# EuroProtoFront.net
KiCad netlist of a schematic drawn in EAGLE
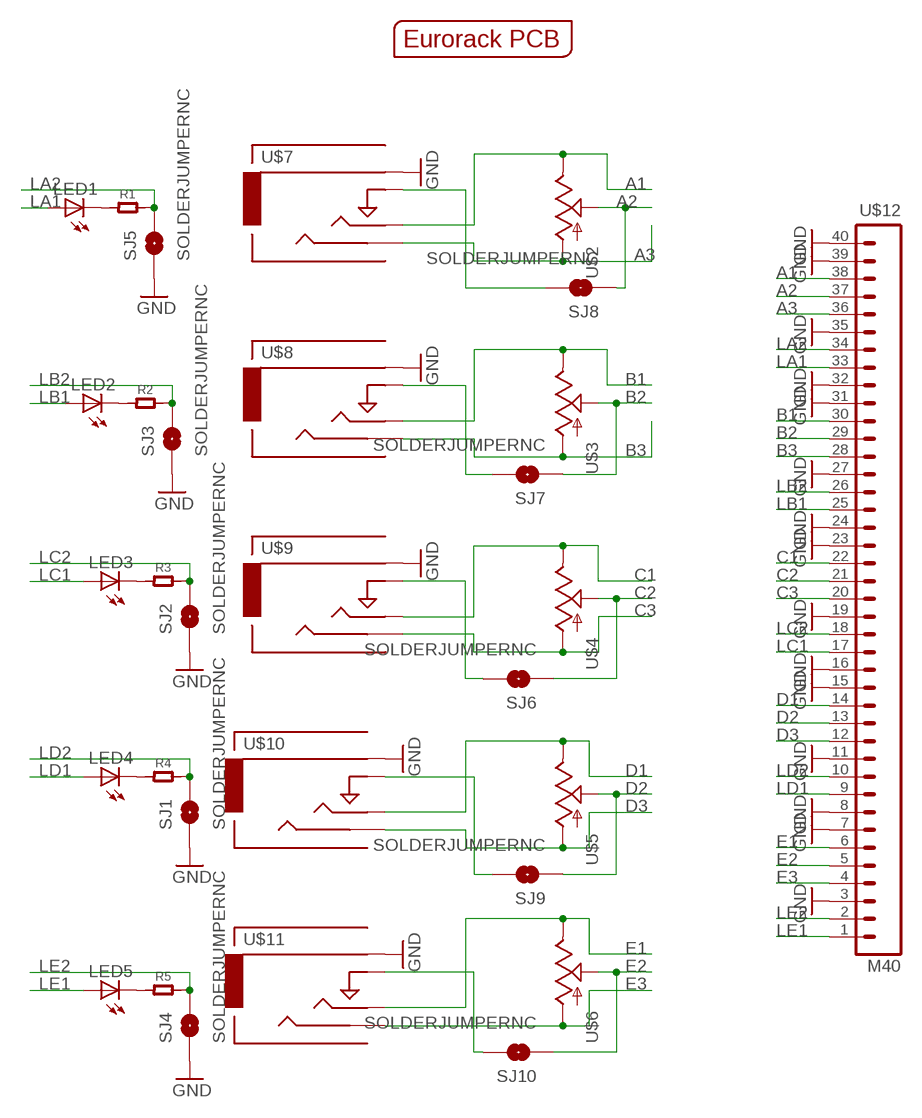
[diagram p0: schematic, sheet 1]

(export (version "E")
  (design (tool "Eeschema 10.0.6"))
  (components
    (comp (ref "LED1")
      (value "LED3MM")
      (footprint "eagle-import:LED3MM")
      (libsource (lib "eagle-import") (part "LED3MM"))
    )
    (comp (ref "LED2")
      (value "LED3MM")
      (footprint "eagle-import:LED3MM")
      (libsource (lib "eagle-import") (part "LED3MM"))
    )
    (comp (ref "LED3")
      (value "LED3MM")
      (footprint "eagle-import:LED3MM")
      (libsource (lib "eagle-import") (part "LED3MM"))
    )
    (comp (ref "LED4")
      (value "LED3MM")
      (footprint "eagle-import:LED3MM")
      (libsource (lib "eagle-import") (part "LED3MM"))
    )
    (comp (ref "LED5")
      (value "LED3MM")
      (footprint "eagle-import:LED3MM")
      (libsource (lib "eagle-import") (part "LED3MM"))
    )
    (comp (ref "R1")
      (value "R-0603")
      (footprint "eagle-import:R0603")
      (libsource (lib "eagle-import") (part "R-0603"))
    )
    (comp (ref "R2")
      (value "R-0603")
      (footprint "eagle-import:R0603")
      (libsource (lib "eagle-import") (part "R-0603"))
    )
    (comp (ref "R3")
      (value "R-0603")
      (footprint "eagle-import:R0603")
      (libsource (lib "eagle-import") (part "R-0603"))
    )
    (comp (ref "R4")
      (value "R-0603")
      (footprint "eagle-import:R0603")
      (libsource (lib "eagle-import") (part "R-0603"))
    )
    (comp (ref "R5")
      (value "R-0603")
      (footprint "eagle-import:R0603")
      (libsource (lib "eagle-import") (part "R-0603"))
    )
    (comp (ref "SJ1")
      (value "SOLDERJUMPERNC")
      (footprint "eagle-import:SJ_2S")
      (libsource (lib "eagle-import") (part "SOLDERJUMPERNC"))
    )
    (comp (ref "SJ2")
      (value "SOLDERJUMPERNC")
      (footprint "eagle-import:SJ_2S")
      (libsource (lib "eagle-import") (part "SOLDERJUMPERNC"))
    )
    (comp (ref "SJ3")
      (value "SOLDERJUMPERNC")
      (footprint "eagle-import:SJ_2S")
      (libsource (lib "eagle-import") (part "SOLDERJUMPERNC"))
    )
    (comp (ref "SJ4")
      (value "SOLDERJUMPERNC")
      (footprint "eagle-import:SJ_2S")
      (libsource (lib "eagle-import") (part "SOLDERJUMPERNC"))
    )
    (comp (ref "SJ5")
      (value "SOLDERJUMPERNC")
      (footprint "eagle-import:SJ_2S")
      (libsource (lib "eagle-import") (part "SOLDERJUMPERNC"))
    )
    (comp (ref "SJ6")
      (value "SOLDERJUMPERNC")
      (footprint "eagle-import:SJ_2S")
      (libsource (lib "eagle-import") (part "SOLDERJUMPERNC"))
    )
    (comp (ref "SJ7")
      (value "SOLDERJUMPERNC")
      (footprint "eagle-import:SJ_2S")
      (libsource (lib "eagle-import") (part "SOLDERJUMPERNC"))
    )
    (comp (ref "SJ8")
      (value "SOLDERJUMPERNC")
      (footprint "eagle-import:SJ_2S")
      (libsource (lib "eagle-import") (part "SOLDERJUMPERNC"))
    )
    (comp (ref "SJ9")
      (value "SOLDERJUMPERNC")
      (footprint "eagle-import:SJ_2S")
      (libsource (lib "eagle-import") (part "SOLDERJUMPERNC"))
    )
    (comp (ref "SJ10")
      (value "SOLDERJUMPERNC")
      (footprint "eagle-import:SJ_2S")
      (libsource (lib "eagle-import") (part "SOLDERJUMPERNC"))
    )
    (comp (ref "U$1")
      (value "EURORACK_PCB4HP")
      (footprint "eagle-import:EURORACK4HPPCB")
      (libsource (lib "eagle-import") (part "EURORACK_PCB4HP"))
    )
    (comp (ref "U$2")
      (value "POTZEPHPOT")
      (footprint "eagle-import:OG-POTS_ALPS_POT_VERTICAL")
      (libsource (lib "eagle-import") (part "POTZEPHPOT"))
    )
    (comp (ref "U$3")
      (value "POTZEPHPOT")
      (footprint "eagle-import:OG-POTS_ALPS_POT_VERTICAL")
      (libsource (lib "eagle-import") (part "POTZEPHPOT"))
    )
    (comp (ref "U$4")
      (value "POTZEPHPOT")
      (footprint "eagle-import:OG-POTS_ALPS_POT_VERTICAL")
      (libsource (lib "eagle-import") (part "POTZEPHPOT"))
    )
    (comp (ref "U$5")
      (value "POTZEPHPOT")
      (footprint "eagle-import:OG-POTS_ALPS_POT_VERTICAL")
      (libsource (lib "eagle-import") (part "POTZEPHPOT"))
    )
    (comp (ref "U$6")
      (value "POTZEPHPOT")
      (footprint "eagle-import:OG-POTS_ALPS_POT_VERTICAL")
      (libsource (lib "eagle-import") (part "POTZEPHPOT"))
    )
    (comp (ref "U$7")
      (value "AUDIO-JACKINPUT")
      (footprint "eagle-import:3.5MM-JACK-SWITCH-13MM-INPUT")
      (libsource (lib "eagle-import") (part "AUDIO-JACKINPUT"))
    )
    (comp (ref "U$8")
      (value "AUDIO-JACKINPUT")
      (footprint "eagle-import:3.5MM-JACK-SWITCH-13MM-INPUT")
      (libsource (lib "eagle-import") (part "AUDIO-JACKINPUT"))
    )
    (comp (ref "U$9")
      (value "AUDIO-JACKINPUT")
      (footprint "eagle-import:3.5MM-JACK-SWITCH-13MM-INPUT")
      (libsource (lib "eagle-import") (part "AUDIO-JACKINPUT"))
    )
    (comp (ref "U$10")
      (value "AUDIO-JACKINPUT")
      (footprint "eagle-import:3.5MM-JACK-SWITCH-13MM-INPUT")
      (libsource (lib "eagle-import") (part "AUDIO-JACKINPUT"))
    )
    (comp (ref "U$11")
      (value "AUDIO-JACKINPUT")
      (footprint "eagle-import:3.5MM-JACK-SWITCH-13MM-INPUT")
      (libsource (lib "eagle-import") (part "AUDIO-JACKINPUT"))
    )
    (comp (ref "U$12")
      (value "M40")
      (footprint "eagle-import:1X40")
      (libsource (lib "eagle-import") (part "M40"))
    )
  )
  (nets
    (net (code "1") (name "/A1") (class "Default")
      (node (ref "U$12") (pin "38") (pinfunction "38_38") (pintype "passive"))
      (node (ref "U$2") (pin "P$1") (pinfunction "E_P$1") (pintype "passive"))
      (node (ref "U$7") (pin "TIP@1") (pinfunction "TIP_TIP@1") (pintype "bidirectional"))
      (node (ref "U$7") (pin "TIP@2") (pinfunction "TIP_TIP@2") (pintype "bidirectional"))
    )
    (net (code "2") (name "/A2") (class "Default")
      (node (ref "SJ8") (pin "1") (pinfunction "1_1") (pintype "passive"))
      (node (ref "U$12") (pin "37") (pinfunction "37_37") (pintype "passive"))
      (node (ref "U$2") (pin "P$2") (pinfunction "S_P$2") (pintype "passive"))
    )
    (net (code "3") (name "/A3") (class "Default")
      (node (ref "U$12") (pin "36") (pinfunction "36_36") (pintype "passive"))
      (node (ref "U$2") (pin "P$3") (pinfunction "A_P$3") (pintype "passive"))
      (node (ref "U$7") (pin "SECOND@1") (pinfunction "SECOND_SECOND@1") (pintype "bidirectional"))
      (node (ref "U$7") (pin "SECOND@2") (pinfunction "SECOND_SECOND@2") (pintype "bidirectional"))
    )
    (net (code "4") (name "/B1") (class "Default")
      (node (ref "U$12") (pin "30") (pinfunction "30_30") (pintype "passive"))
      (node (ref "U$3") (pin "P$1") (pinfunction "E_P$1") (pintype "passive"))
      (node (ref "U$8") (pin "TIP@1") (pinfunction "TIP_TIP@1") (pintype "bidirectional"))
      (node (ref "U$8") (pin "TIP@2") (pinfunction "TIP_TIP@2") (pintype "bidirectional"))
    )
    (net (code "5") (name "/B2") (class "Default")
      (node (ref "SJ7") (pin "1") (pinfunction "1_1") (pintype "passive"))
      (node (ref "U$12") (pin "29") (pinfunction "29_29") (pintype "passive"))
      (node (ref "U$3") (pin "P$2") (pinfunction "S_P$2") (pintype "passive"))
    )
    (net (code "6") (name "/B3") (class "Default")
      (node (ref "U$12") (pin "28") (pinfunction "28_28") (pintype "passive"))
      (node (ref "U$3") (pin "P$3") (pinfunction "A_P$3") (pintype "passive"))
      (node (ref "U$8") (pin "SECOND@1") (pinfunction "SECOND_SECOND@1") (pintype "bidirectional"))
      (node (ref "U$8") (pin "SECOND@2") (pinfunction "SECOND_SECOND@2") (pintype "bidirectional"))
    )
    (net (code "7") (name "/C1") (class "Default")
      (node (ref "U$12") (pin "22") (pinfunction "22_22") (pintype "passive"))
      (node (ref "U$4") (pin "P$1") (pinfunction "E_P$1") (pintype "passive"))
      (node (ref "U$9") (pin "TIP@1") (pinfunction "TIP_TIP@1") (pintype "bidirectional"))
      (node (ref "U$9") (pin "TIP@2") (pinfunction "TIP_TIP@2") (pintype "bidirectional"))
    )
    (net (code "8") (name "/C2") (class "Default")
      (node (ref "SJ6") (pin "1") (pinfunction "1_1") (pintype "passive"))
      (node (ref "U$12") (pin "21") (pinfunction "21_21") (pintype "passive"))
      (node (ref "U$4") (pin "P$2") (pinfunction "S_P$2") (pintype "passive"))
    )
    (net (code "9") (name "/C3") (class "Default")
      (node (ref "U$12") (pin "20") (pinfunction "20_20") (pintype "passive"))
      (node (ref "U$4") (pin "P$3") (pinfunction "A_P$3") (pintype "passive"))
      (node (ref "U$9") (pin "SECOND@1") (pinfunction "SECOND_SECOND@1") (pintype "bidirectional"))
      (node (ref "U$9") (pin "SECOND@2") (pinfunction "SECOND_SECOND@2") (pintype "bidirectional"))
    )
    (net (code "10") (name "/D1") (class "Default")
      (node (ref "U$10") (pin "TIP@1") (pinfunction "TIP_TIP@1") (pintype "bidirectional"))
      (node (ref "U$10") (pin "TIP@2") (pinfunction "TIP_TIP@2") (pintype "bidirectional"))
      (node (ref "U$12") (pin "14") (pinfunction "14_14") (pintype "passive"))
      (node (ref "U$5") (pin "P$1") (pinfunction "E_P$1") (pintype "passive"))
    )
    (net (code "11") (name "/D2") (class "Default")
      (node (ref "SJ9") (pin "1") (pinfunction "1_1") (pintype "passive"))
      (node (ref "U$12") (pin "13") (pinfunction "13_13") (pintype "passive"))
      (node (ref "U$5") (pin "P$2") (pinfunction "S_P$2") (pintype "passive"))
    )
    (net (code "12") (name "/D3") (class "Default")
      (node (ref "U$10") (pin "SECOND@1") (pinfunction "SECOND_SECOND@1") (pintype "bidirectional"))
      (node (ref "U$10") (pin "SECOND@2") (pinfunction "SECOND_SECOND@2") (pintype "bidirectional"))
      (node (ref "U$12") (pin "12") (pinfunction "12_12") (pintype "passive"))
      (node (ref "U$5") (pin "P$3") (pinfunction "A_P$3") (pintype "passive"))
    )
    (net (code "13") (name "/E1") (class "Default")
      (node (ref "U$11") (pin "TIP@1") (pinfunction "TIP_TIP@1") (pintype "bidirectional"))
      (node (ref "U$11") (pin "TIP@2") (pinfunction "TIP_TIP@2") (pintype "bidirectional"))
      (node (ref "U$12") (pin "6") (pinfunction "6_6") (pintype "passive"))
      (node (ref "U$6") (pin "P$1") (pinfunction "E_P$1") (pintype "passive"))
    )
    (net (code "14") (name "/E2") (class "Default")
      (node (ref "SJ10") (pin "1") (pinfunction "1_1") (pintype "passive"))
      (node (ref "U$12") (pin "5") (pinfunction "5_5") (pintype "passive"))
      (node (ref "U$6") (pin "P$2") (pinfunction "S_P$2") (pintype "passive"))
    )
    (net (code "15") (name "/E3") (class "Default")
      (node (ref "U$11") (pin "SECOND@1") (pinfunction "SECOND_SECOND@1") (pintype "bidirectional"))
      (node (ref "U$11") (pin "SECOND@2") (pinfunction "SECOND_SECOND@2") (pintype "bidirectional"))
      (node (ref "U$12") (pin "4") (pinfunction "4_4") (pintype "passive"))
      (node (ref "U$6") (pin "P$3") (pinfunction "A_P$3") (pintype "passive"))
    )
    (net (code "16") (name "/LA1") (class "Default")
      (node (ref "LED1") (pin "A") (pinfunction "A_A") (pintype "passive"))
      (node (ref "U$12") (pin "33") (pinfunction "33_33") (pintype "passive"))
    )
    (net (code "17") (name "/LA2") (class "Default")
      (node (ref "R1") (pin "2") (pinfunction "2_2") (pintype "bidirectional"))
      (node (ref "SJ5") (pin "2") (pinfunction "2_2") (pintype "passive"))
      (node (ref "U$12") (pin "34") (pinfunction "34_34") (pintype "passive"))
    )
    (net (code "18") (name "/LB1") (class "Default")
      (node (ref "LED2") (pin "A") (pinfunction "A_A") (pintype "passive"))
      (node (ref "U$12") (pin "25") (pinfunction "25_25") (pintype "passive"))
    )
    (net (code "19") (name "/LB2") (class "Default")
      (node (ref "R2") (pin "2") (pinfunction "2_2") (pintype "bidirectional"))
      (node (ref "SJ3") (pin "2") (pinfunction "2_2") (pintype "passive"))
      (node (ref "U$12") (pin "26") (pinfunction "26_26") (pintype "passive"))
    )
    (net (code "20") (name "/LC1") (class "Default")
      (node (ref "LED3") (pin "A") (pinfunction "A_A") (pintype "passive"))
      (node (ref "U$12") (pin "17") (pinfunction "17_17") (pintype "passive"))
    )
    (net (code "21") (name "/LC2") (class "Default")
      (node (ref "R3") (pin "2") (pinfunction "2_2") (pintype "bidirectional"))
      (node (ref "SJ2") (pin "2") (pinfunction "2_2") (pintype "passive"))
      (node (ref "U$12") (pin "18") (pinfunction "18_18") (pintype "passive"))
    )
    (net (code "22") (name "/LD1") (class "Default")
      (node (ref "LED4") (pin "A") (pinfunction "A_A") (pintype "passive"))
      (node (ref "U$12") (pin "9") (pinfunction "9_9") (pintype "passive"))
    )
    (net (code "23") (name "/LD2") (class "Default")
      (node (ref "R4") (pin "2") (pinfunction "2_2") (pintype "bidirectional"))
      (node (ref "SJ1") (pin "2") (pinfunction "2_2") (pintype "passive"))
      (node (ref "U$12") (pin "10") (pinfunction "10_10") (pintype "passive"))
    )
    (net (code "24") (name "/LE1") (class "Default")
      (node (ref "LED5") (pin "A") (pinfunction "A_A") (pintype "passive"))
      (node (ref "U$12") (pin "1") (pinfunction "1_1") (pintype "passive"))
    )
    (net (code "25") (name "/LE2") (class "Default")
      (node (ref "R5") (pin "2") (pinfunction "2_2") (pintype "bidirectional"))
      (node (ref "SJ4") (pin "2") (pinfunction "2_2") (pintype "passive"))
      (node (ref "U$12") (pin "2") (pinfunction "2_2") (pintype "passive"))
    )
    (net (code "26") (name "GND") (class "Default")
      (node (ref "SJ1") (pin "1") (pinfunction "1_1") (pintype "passive"))
      (node (ref "SJ2") (pin "1") (pinfunction "1_1") (pintype "passive"))
      (node (ref "SJ3") (pin "1") (pinfunction "1_1") (pintype "passive"))
      (node (ref "SJ4") (pin "1") (pinfunction "1_1") (pintype "passive"))
      (node (ref "SJ5") (pin "1") (pinfunction "1_1") (pintype "passive"))
      (node (ref "U$10") (pin "RING@1") (pinfunction "RING_RING@1") (pintype "bidirectional"))
      (node (ref "U$10") (pin "RING@2") (pinfunction "RING_RING@2") (pintype "bidirectional"))
      (node (ref "U$11") (pin "RING@1") (pinfunction "RING_RING@1") (pintype "bidirectional"))
      (node (ref "U$11") (pin "RING@2") (pinfunction "RING_RING@2") (pintype "bidirectional"))
      (node (ref "U$12") (pin "11") (pinfunction "11_11") (pintype "passive"))
      (node (ref "U$12") (pin "15") (pinfunction "15_15") (pintype "passive"))
      (node (ref "U$12") (pin "16") (pinfunction "16_16") (pintype "passive"))
      (node (ref "U$12") (pin "19") (pinfunction "19_19") (pintype "passive"))
      (node (ref "U$12") (pin "23") (pinfunction "23_23") (pintype "passive"))
      (node (ref "U$12") (pin "24") (pinfunction "24_24") (pintype "passive"))
      (node (ref "U$12") (pin "27") (pinfunction "27_27") (pintype "passive"))
      (node (ref "U$12") (pin "3") (pinfunction "3_3") (pintype "passive"))
      (node (ref "U$12") (pin "31") (pinfunction "31_31") (pintype "passive"))
      (node (ref "U$12") (pin "32") (pinfunction "32_32") (pintype "passive"))
      (node (ref "U$12") (pin "35") (pinfunction "35_35") (pintype "passive"))
      (node (ref "U$12") (pin "39") (pinfunction "39_39") (pintype "passive"))
      (node (ref "U$12") (pin "40") (pinfunction "40_40") (pintype "passive"))
      (node (ref "U$12") (pin "7") (pinfunction "7_7") (pintype "passive"))
      (node (ref "U$12") (pin "8") (pinfunction "8_8") (pintype "passive"))
      (node (ref "U$7") (pin "RING@1") (pinfunction "RING_RING@1") (pintype "bidirectional"))
      (node (ref "U$7") (pin "RING@2") (pinfunction "RING_RING@2") (pintype "bidirectional"))
      (node (ref "U$8") (pin "RING@1") (pinfunction "RING_RING@1") (pintype "bidirectional"))
      (node (ref "U$8") (pin "RING@2") (pinfunction "RING_RING@2") (pintype "bidirectional"))
      (node (ref "U$9") (pin "RING@1") (pinfunction "RING_RING@1") (pintype "bidirectional"))
      (node (ref "U$9") (pin "RING@2") (pinfunction "RING_RING@2") (pintype "bidirectional"))
    )
    (net (code "27") (name "Net-(LED1-C)") (class "Default")
      (node (ref "LED1") (pin "K") (pinfunction "C_K") (pintype "passive"))
      (node (ref "R1") (pin "1") (pinfunction "1_1") (pintype "bidirectional"))
    )
    (net (code "28") (name "Net-(LED2-C)") (class "Default")
      (node (ref "LED2") (pin "K") (pinfunction "C_K") (pintype "passive"))
      (node (ref "R2") (pin "1") (pinfunction "1_1") (pintype "bidirectional"))
    )
    (net (code "29") (name "Net-(LED3-C)") (class "Default")
      (node (ref "LED3") (pin "K") (pinfunction "C_K") (pintype "passive"))
      (node (ref "R3") (pin "1") (pinfunction "1_1") (pintype "bidirectional"))
    )
    (net (code "30") (name "Net-(LED4-C)") (class "Default")
      (node (ref "LED4") (pin "K") (pinfunction "C_K") (pintype "passive"))
      (node (ref "R4") (pin "1") (pinfunction "1_1") (pintype "bidirectional"))
    )
    (net (code "31") (name "Net-(LED5-C)") (class "Default")
      (node (ref "LED5") (pin "K") (pinfunction "C_K") (pintype "passive"))
      (node (ref "R5") (pin "1") (pinfunction "1_1") (pintype "bidirectional"))
    )
    (net (code "32") (name "Net-(SJ6-Pad2)") (class "Default")
      (node (ref "SJ6") (pin "2") (pinfunction "2_2") (pintype "passive"))
      (node (ref "U$9") (pin "SWITCH@1") (pinfunction "SWITCH_SWITCH@1") (pintype "bidirectional"))
      (node (ref "U$9") (pin "SWITCH@2") (pinfunction "SWITCH_SWITCH@2") (pintype "bidirectional"))
    )
    (net (code "33") (name "Net-(SJ7-Pad2)") (class "Default")
      (node (ref "SJ7") (pin "2") (pinfunction "2_2") (pintype "passive"))
      (node (ref "U$8") (pin "SWITCH@1") (pinfunction "SWITCH_SWITCH@1") (pintype "bidirectional"))
      (node (ref "U$8") (pin "SWITCH@2") (pinfunction "SWITCH_SWITCH@2") (pintype "bidirectional"))
    )
    (net (code "34") (name "Net-(SJ8-Pad2)") (class "Default")
      (node (ref "SJ8") (pin "2") (pinfunction "2_2") (pintype "passive"))
      (node (ref "U$7") (pin "SWITCH@1") (pinfunction "SWITCH_SWITCH@1") (pintype "bidirectional"))
      (node (ref "U$7") (pin "SWITCH@2") (pinfunction "SWITCH_SWITCH@2") (pintype "bidirectional"))
    )
    (net (code "35") (name "Net-(SJ9-Pad2)") (class "Default")
      (node (ref "SJ9") (pin "2") (pinfunction "2_2") (pintype "passive"))
      (node (ref "U$10") (pin "SWITCH@1") (pinfunction "SWITCH_SWITCH@1") (pintype "bidirectional"))
      (node (ref "U$10") (pin "SWITCH@2") (pinfunction "SWITCH_SWITCH@2") (pintype "bidirectional"))
    )
    (net (code "36") (name "Net-(SJ10-Pad2)") (class "Default")
      (node (ref "SJ10") (pin "2") (pinfunction "2_2") (pintype "passive"))
      (node (ref "U$11") (pin "SWITCH@1") (pinfunction "SWITCH_SWITCH@1") (pintype "bidirectional"))
      (node (ref "U$11") (pin "SWITCH@2") (pinfunction "SWITCH_SWITCH@2") (pintype "bidirectional"))
    )
  )
)
